# esp32_with_usbc_1st.net
KiCad netlist of a schematic drawn in Altium Designer
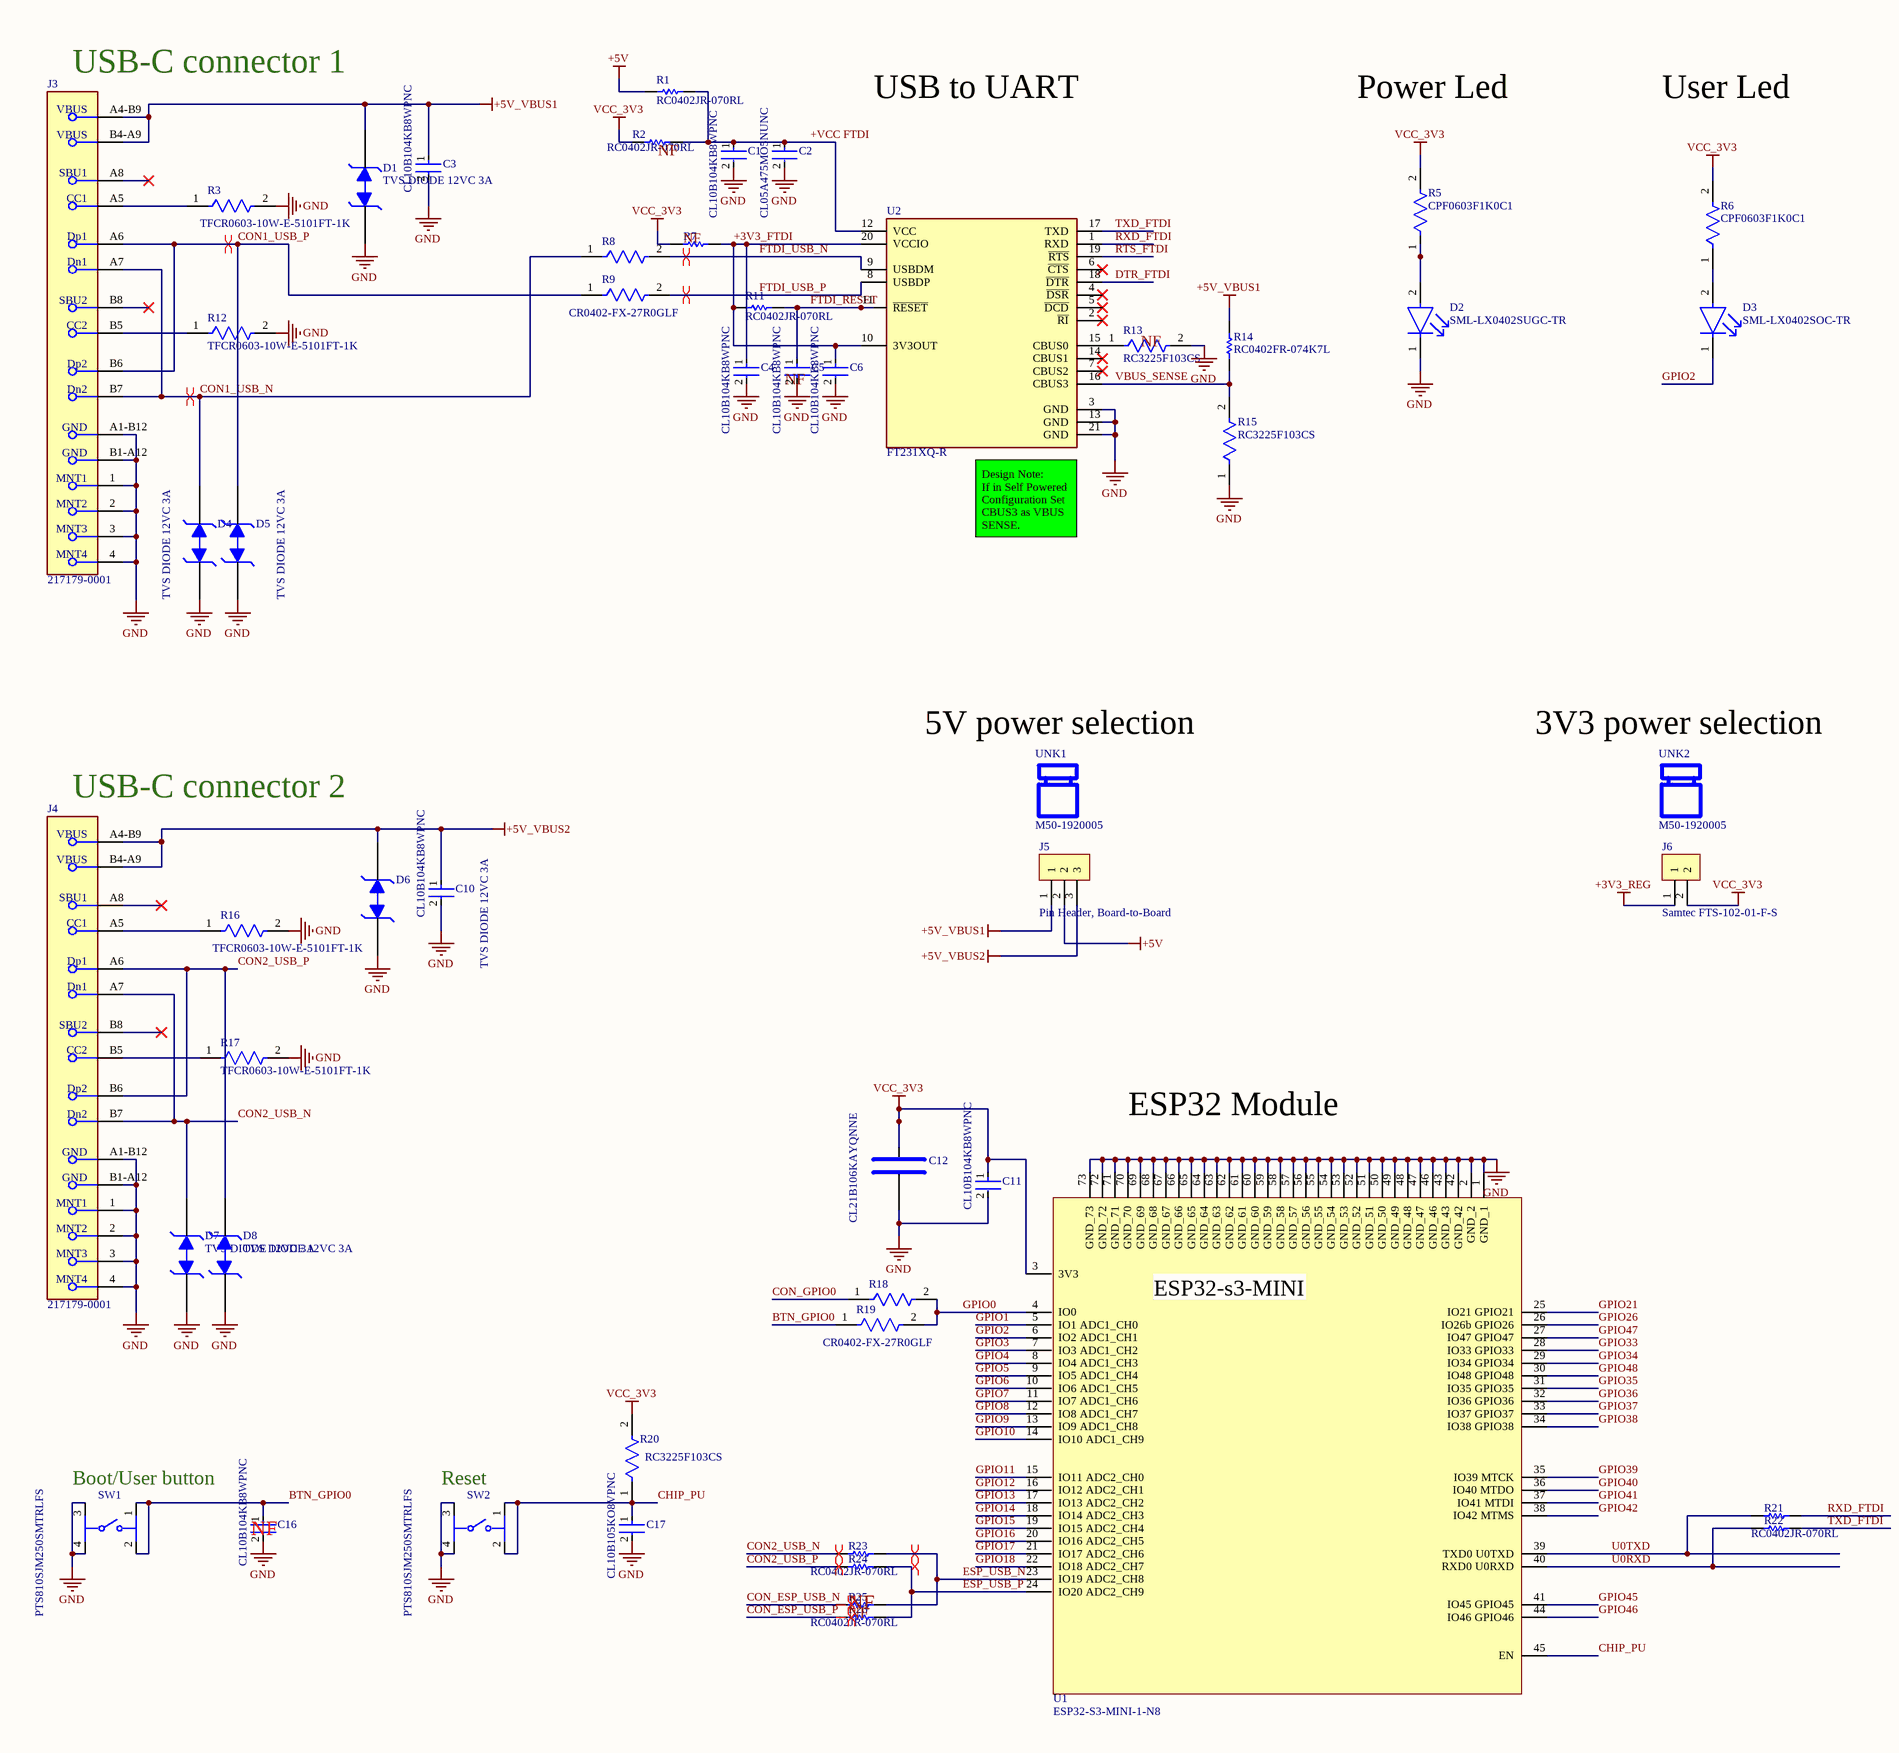
[diagram p0: esp32_with_usbc_1st.SchDoc, left]
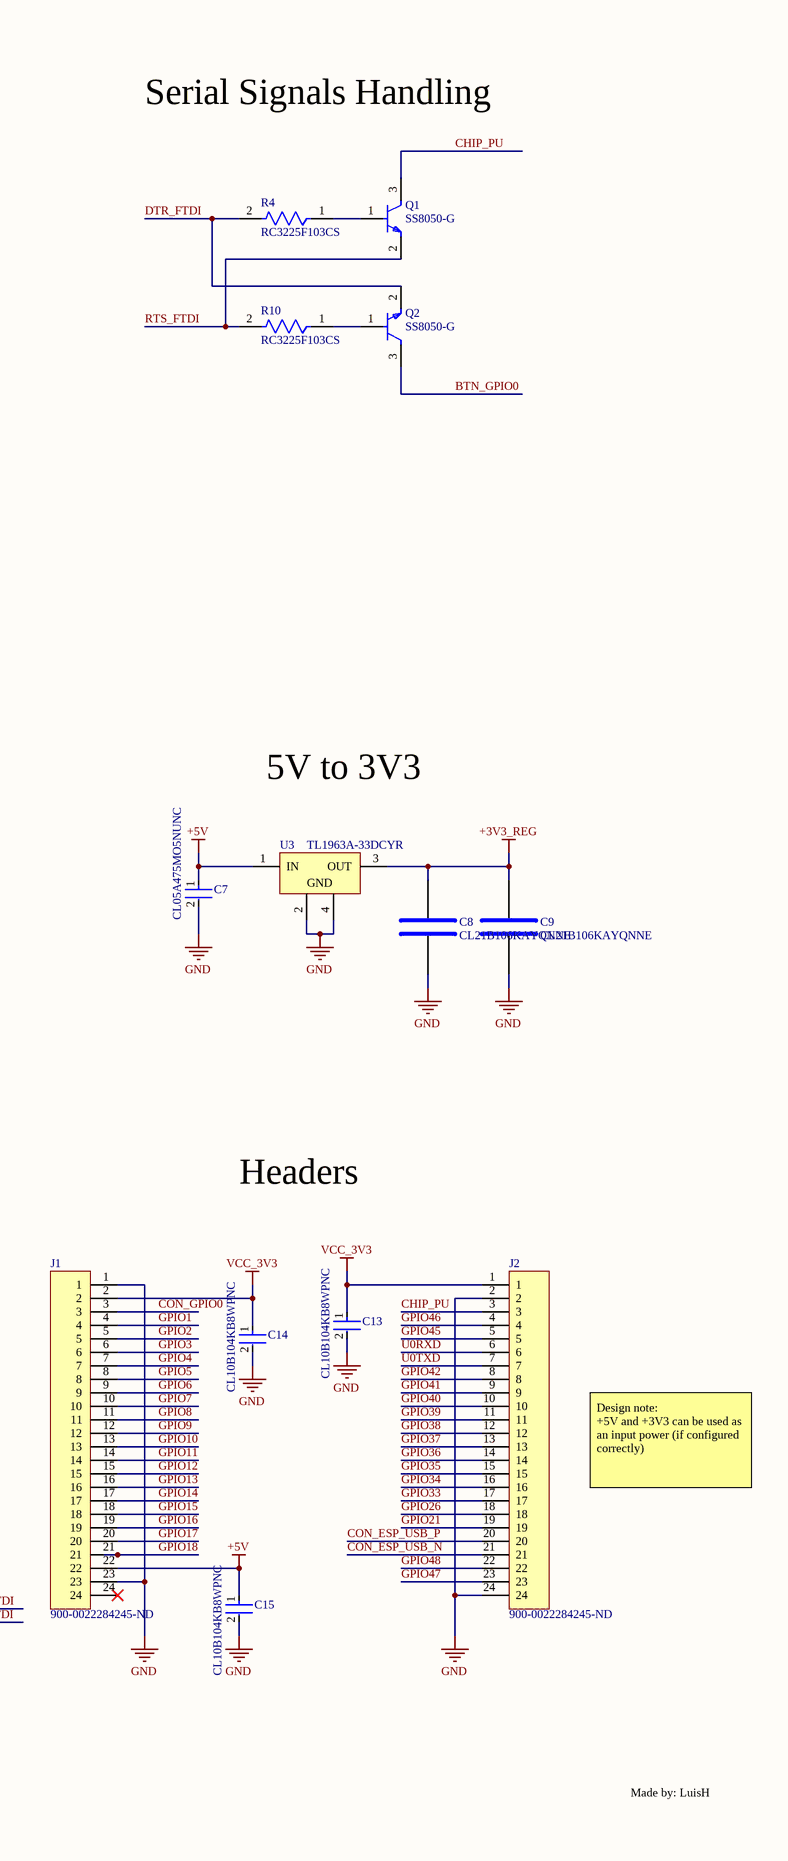
[diagram p1: esp32_with_usbc_1st.SchDoc, right]

(export (version "E")
  (design (tool "Eeschema 10.0.6"))
  (components
    (comp (ref "C1")
      (value "CL10B104KB8WPNC")
      (footprint "FP-CL10-IPC_A")
      (description "Cap Ceramic 100nF 50V X7R ±10% Pad SMD 0603 +125°C T/R")
      (fields (field (name "TOLERANCE") "10%"))
      (libsource (lib "Altium Content Vault") (part "b4654b650e69147ec39a6b967a45e02"))
    )
    (comp (ref "C2")
      (value "CL05A475MO5NUNC")
      (footprint "FP-CL829-IPC_C")
      (description "Cap Ceramic 4.7uF 16V X5R ±20% SMD 0402 +85°C Paper T/R")
      (fields (field (name "TOLERANCE") "20%"))
      (libsource (lib "Altium Content Vault") (part "b4654b650e69147ec39a6b967a45e02"))
    )
    (comp (ref "C3")
      (value "CL10B104KB8WPNC")
      (footprint "FP-CL10-IPC_A")
      (description "Cap Ceramic 100nF 50V X7R ±10% Pad SMD 0603 +125°C T/R")
      (fields (field (name "TOLERANCE") "10%"))
      (libsource (lib "Altium Content Vault") (part "b4654b650e69147ec39a6b967a45e02"))
    )
    (comp (ref "C4")
      (value "CL10B104KB8WPNC")
      (footprint "FP-CL10-IPC_A")
      (description "Cap Ceramic 100nF 50V X7R ±10% Pad SMD 0603 +125°C T/R")
      (fields (field (name "TOLERANCE") "10%"))
      (libsource (lib "Altium Content Vault") (part "b4654b650e69147ec39a6b967a45e02"))
    )
    (comp (ref "C5")
      (value "CL10B104KB8WPNC")
      (footprint "FP-CL10-IPC_A")
      (description "Cap Ceramic 100nF 50V X7R ±10% Pad SMD 0603 +125°C T/R")
      (fields (field (name "TOLERANCE") "10%"))
      (libsource (lib "Altium Content Vault") (part "b4654b650e69147ec39a6b967a45e02"))
    )
    (comp (ref "C6")
      (value "CL10B104KB8WPNC")
      (footprint "FP-CL10-IPC_A")
      (description "Cap Ceramic 100nF 50V X7R ±10% Pad SMD 0603 +125°C T/R")
      (fields (field (name "TOLERANCE") "10%"))
      (libsource (lib "Altium Content Vault") (part "b4654b650e69147ec39a6b967a45e02"))
    )
    (comp (ref "C7")
      (value "CL05A475MO5NUNC")
      (footprint "FP-CL829-IPC_C")
      (description "Cap Ceramic 4.7uF 16V X5R ±20% SMD 0402 +85°C Paper T/R")
      (fields (field (name "TOLERANCE") "20%"))
      (libsource (lib "Altium Content Vault") (part "b4654b650e69147ec39a6b967a45e02"))
    )
    (comp (ref "C8")
      (value "CL21B106KAYQNNE")
      (footprint "CAP_CL21B106KAYQNNE_SAM-L")
      (description "25V 10uF X7R 卤10% 0805 Multilayer Ceramic Capacitors MLCC - SMD/SMT ROHS")
      (fields (field (name "MANUFACTURER") "Samsung Electro-Mechanics") (field (name "TOLERANCE") "10%"))
      (libsource (lib "esp32_with_usbc") (part "CL21B106KAYQNNE"))
    )
    (comp (ref "C9")
      (value "CL21B106KAYQNNE")
      (footprint "CAP_CL21B106KAYQNNE_SAM-L")
      (description "25V 10uF X7R 卤10% 0805 Multilayer Ceramic Capacitors MLCC - SMD/SMT ROHS")
      (fields (field (name "MANUFACTURER") "Samsung Electro-Mechanics") (field (name "TOLERANCE") "10%"))
      (libsource (lib "esp32_with_usbc") (part "CL21B106KAYQNNE"))
    )
    (comp (ref "C10")
      (value "CL10B104KB8WPNC")
      (footprint "FP-CL10-IPC_A")
      (description "Cap Ceramic 100nF 50V X7R ±10% Pad SMD 0603 +125°C T/R")
      (fields (field (name "TOLERANCE") "10%"))
      (libsource (lib "Altium Content Vault") (part "b4654b650e69147ec39a6b967a45e02"))
    )
    (comp (ref "C11")
      (value "CL10B104KB8WPNC")
      (footprint "FP-CL10-IPC_A")
      (description "Cap Ceramic 100nF 50V X7R ±10% Pad SMD 0603 +125°C T/R")
      (fields (field (name "TOLERANCE") "10%"))
      (libsource (lib "Altium Content Vault") (part "b4654b650e69147ec39a6b967a45e02"))
    )
    (comp (ref "C12")
      (value "CL21B106KAYQNNE")
      (footprint "CAP_CL21B106KAYQNNE_SAM-L")
      (description "25V 10uF X7R 卤10% 0805 Multilayer Ceramic Capacitors MLCC - SMD/SMT ROHS")
      (fields (field (name "MANUFACTURER") "Samsung Electro-Mechanics") (field (name "TOLERANCE") "10%"))
      (libsource (lib "esp32_with_usbc") (part "CL21B106KAYQNNE"))
    )
    (comp (ref "C13")
      (value "CL10B104KB8WPNC")
      (footprint "FP-CL10-IPC_A")
      (description "Cap Ceramic 100nF 50V X7R ±10% Pad SMD 0603 +125°C T/R")
      (fields (field (name "TOLERANCE") "10%"))
      (libsource (lib "Altium Content Vault") (part "b4654b650e69147ec39a6b967a45e02"))
    )
    (comp (ref "C14")
      (value "CL10B104KB8WPNC")
      (footprint "FP-CL10-IPC_A")
      (description "Cap Ceramic 100nF 50V X7R ±10% Pad SMD 0603 +125°C T/R")
      (fields (field (name "TOLERANCE") "10%"))
      (libsource (lib "Altium Content Vault") (part "b4654b650e69147ec39a6b967a45e02"))
    )
    (comp (ref "C15")
      (value "CL10B104KB8WPNC")
      (footprint "FP-CL10-IPC_A")
      (description "Cap Ceramic 100nF 50V X7R ±10% Pad SMD 0603 +125°C T/R")
      (fields (field (name "TOLERANCE") "10%"))
      (libsource (lib "Altium Content Vault") (part "b4654b650e69147ec39a6b967a45e02"))
    )
    (comp (ref "C16")
      (value "CL10B104KB8WPNC")
      (footprint "FP-CL10-IPC_A")
      (description "Cap Ceramic 100nF 50V X7R ±10% Pad SMD 0603 +125°C T/R")
      (fields (field (name "TOLERANCE") "10%"))
      (libsource (lib "Altium Content Vault") (part "b4654b650e69147ec39a6b967a45e02"))
    )
    (comp (ref "C17")
      (value "CL10B105KO8VPNC")
      (footprint "FP-CL10-IPC_C")
      (description "Cap Ceramic 1uF 16V X7R ±10% Pad SMD 0603 +125°C T/R")
      (fields (field (name "TOLERANCE") "10%"))
      (libsource (lib "Altium Content Vault") (part "b4654b650e69147ec39a6b967a45e02"))
    )
    (comp (ref "D1")
      (value "TVS DIODE 12VC 3A")
      (footprint "RTVS_SOD882_LTF")
      (description "TVS DIODE 12VC 3A SOD882 / ESD Suppressor TVS Bi-Dir 5.3V Automotive 2-Pin SOD-882 T/R")
      (fields
        (field (name "MANUFACTURER") "Littelfuse")
        (field (name "MANUFACTURER PART NUMBER") "AQ3045-01ETG")
      )
      (libsource (lib "esp32_with_usbc") (part "AQ3045-01ETG"))
    )
    (comp (ref "D2")
      (value "SML-LX0402SUGC-TR")
      (footprint "FP-SML-LX0402SUGC-TR-MFG")
      (description "LED GREEN CLEAR SMD")
      (libsource (lib "Altium Content Vault") (part "8706943c75ba83719d021d2fdc84c58"))
    )
    (comp (ref "D3")
      (value "SML-LX0402SOC-TR")
      (footprint "FP-SML-LX0402SOC-TR-MFG")
      (description "LED ORANGE CLEAR SMD")
      (libsource (lib "Altium Content Vault") (part "8706943c75ba83719d021d2fdc84c58"))
    )
    (comp (ref "D4")
      (value "TVS DIODE 12VC 3A")
      (footprint "RTVS_SOD882_LTF")
      (description "TVS DIODE 12VC 3A SOD882 / ESD Suppressor TVS Bi-Dir 5.3V Automotive 2-Pin SOD-882 T/R")
      (fields
        (field (name "MANUFACTURER") "Littelfuse")
        (field (name "MANUFACTURER PART NUMBER") "AQ3045-01ETG")
      )
      (libsource (lib "esp32_with_usbc") (part "AQ3045-01ETG"))
    )
    (comp (ref "D5")
      (value "TVS DIODE 12VC 3A")
      (footprint "RTVS_SOD882_LTF")
      (description "TVS DIODE 12VC 3A SOD882 / ESD Suppressor TVS Bi-Dir 5.3V Automotive 2-Pin SOD-882 T/R")
      (fields
        (field (name "MANUFACTURER") "Littelfuse")
        (field (name "MANUFACTURER PART NUMBER") "AQ3045-01ETG")
      )
      (libsource (lib "esp32_with_usbc") (part "AQ3045-01ETG"))
    )
    (comp (ref "D6")
      (value "TVS DIODE 12VC 3A")
      (footprint "RTVS_SOD882_LTF")
      (description "TVS DIODE 12VC 3A SOD882 / ESD Suppressor TVS Bi-Dir 5.3V Automotive 2-Pin SOD-882 T/R")
      (fields
        (field (name "MANUFACTURER") "Littelfuse")
        (field (name "MANUFACTURER PART NUMBER") "AQ3045-01ETG")
      )
      (libsource (lib "esp32_with_usbc") (part "AQ3045-01ETG"))
    )
    (comp (ref "D7")
      (value "TVS DIODE 12VC 3A")
      (footprint "RTVS_SOD882_LTF")
      (description "TVS DIODE 12VC 3A SOD882 / ESD Suppressor TVS Bi-Dir 5.3V Automotive 2-Pin SOD-882 T/R")
      (fields
        (field (name "MANUFACTURER") "Littelfuse")
        (field (name "MANUFACTURER PART NUMBER") "AQ3045-01ETG")
      )
      (libsource (lib "esp32_with_usbc") (part "AQ3045-01ETG"))
    )
    (comp (ref "D8")
      (value "TVS DIODE 12VC 3A")
      (footprint "RTVS_SOD882_LTF")
      (description "TVS DIODE 12VC 3A SOD882 / ESD Suppressor TVS Bi-Dir 5.3V Automotive 2-Pin SOD-882 T/R")
      (fields
        (field (name "MANUFACTURER") "Littelfuse")
        (field (name "MANUFACTURER PART NUMBER") "AQ3045-01ETG")
      )
      (libsource (lib "esp32_with_usbc") (part "AQ3045-01ETG"))
    )
    (comp (ref "J1")
      (value "900-0022284245-ND")
      (footprint "CONN_SD-42375-001_M295_24_MOL")
      (fields
        (field (name "MANUFACTURER") "Molex")
        (field (name "MANUFACTURER PART NUMBER") "22-28-4245")
        (field (name "LCSC PART NUMBER") "C7145888")
      )
      (libsource (lib "") (part "22-28-4245_1"))
    )
    (comp (ref "J2")
      (value "900-0022284245-ND")
      (footprint "CONN_SD-42375-001_M295_24_MOL")
      (fields
        (field (name "MANUFACTURER") "Molex")
        (field (name "MANUFACTURER PART NUMBER") "22-28-4245")
        (field (name "LCSC PART NUMBER") "C7145888")
      )
      (libsource (lib "esp32_with_usbc") (part "22-28-4245"))
    )
    (comp (ref "J3")
      (value "217179-0001")
      (footprint "FP-2171790001-MFG")
      (description "USB Connector, 16 Contact(s), Female, Right Angle, Surface Mount Terminal, Locking, Receptacle")
      (fields (field (name "MANUFACTURER") "Molex"))
      (libsource (lib "esp32_with_usbc") (part "217179-0001"))
    )
    (comp (ref "J4")
      (value "217179-0001")
      (footprint "FP-2171790001-MFG")
      (description "USB Connector, 16 Contact(s), Female, Right Angle, Surface Mount Terminal, Locking, Receptacle")
      (fields (field (name "MANUFACTURER") "Molex"))
      (libsource (lib "esp32_with_usbc") (part "217179-0001"))
    )
    (comp (ref "J5")
      (value "Pin Header, Board-to-Board")
      (footprint "HDR_1x3_1.27mm")
      (description "Pin Header, Board-to-Board, Wire-to-Board, 3.4 A, 1.27 mm, 1 Rows, 3 Contacts, Through Hole")
      (fields
        (field (name "MANUFACTURER") "Samtec")
        (field (name "MANUFACTURER PART NUMBER") "FTS-103-01-F-S")
      )
      (libsource (lib "esp32_with_usbc") (part "FTS-103-01-F-S"))
    )
    (comp (ref "J6")
      (value "Samtec FTS-102-01-F-S")
      (footprint "HDR_1x2_1.27mm")
      (description "Pin Header, Board-to-Board, 1.27 mm, 1 Rows, 2 Contacts, Through Hole Straight, FTS Series")
      (fields
        (field (name "MANUFACTURER") "Samtec")
        (field (name "MANUFACTURER PART NUMBER") "FTS-102-01-F-S")
      )
      (libsource (lib "esp32_with_usbc") (part "FTS-102-01-F-S"))
    )
    (comp (ref "Q1")
      (value "SS8050-G")
      (footprint "FP-SS8050-G-MFG")
      (description "NPN TRANSISTOR 1.5A 40V SOT-23 R")
      (libsource (lib "Altium Content Vault") (part "2a1388f82443b098dcd57d24ac7632d"))
    )
    (comp (ref "Q2")
      (value "SS8050-G")
      (footprint "FP-SS8050-G-MFG")
      (description "NPN TRANSISTOR 1.5A 40V SOT-23 R")
      (libsource (lib "Altium Content Vault") (part "2a1388f82443b098dcd57d24ac7632d"))
    )
    (comp (ref "R1")
      (value "RC0402JR-070RL")
      (footprint "RESC1005X40X25NL05T10")
      (fields (field (name "MANUFACTURER") "Yageo / Phycomp"))
      (libsource (lib "Altium Content Vault") (part "RES"))
    )
    (comp (ref "R2")
      (value "RC0402JR-070RL")
      (footprint "RESC1005X40X25NL05T10")
      (fields (field (name "MANUFACTURER") "Yageo / Phycomp"))
      (libsource (lib "Altium Content Vault") (part "RES"))
    )
    (comp (ref "R3")
      (value "TFCR0603-10W-E-5101FT-1K")
      (footprint "FP-TFCR0603-IPC_C")
      (description "RES Thin Film,  5.1kΩ, 1%, 0.1W, 25ppm/°C, 0603")
      (libsource (lib "Altium Content Vault") (part "1029c3af85768c4190bb7ad29bc67b5"))
    )
    (comp (ref "R4")
      (value "RC3225F103CS")
      (footprint "FP-RC3225-IPC_C")
      (description "Res Thick Film 1210 10kΩ 1% 0.333W ±100ppm/°C Pad SMD T/R")
      (libsource (lib "Altium Content Vault") (part "1029c3af85768c4190bb7ad29bc67b5"))
    )
    (comp (ref "R5")
      (value "CPF0603F1K0C1")
      (footprint "FP-CPF0603-MFG")
      (description "RES SMD 1.0KΩ 1% 1/16W 0603")
      (fields
        (field (name "OCTOPART") "https://octopart.com/cpf0603f1k0c1-te+connectivity-42013134")
        (field (name "TOLERANCE") "1%")
      )
      (libsource (lib "Altium Content Vault") (part "1029c3af85768c4190bb7ad29bc67b5"))
    )
    (comp (ref "R6")
      (value "CPF0603F1K0C1")
      (footprint "FP-CPF0603-MFG")
      (description "RES SMD 1.0KΩ 1% 1/16W 0603")
      (fields
        (field (name "OCTOPART") "https://octopart.com/cpf0603f1k0c1-te+connectivity-42013134")
        (field (name "TOLERANCE") "1%")
      )
      (libsource (lib "Altium Content Vault") (part "1029c3af85768c4190bb7ad29bc67b5"))
    )
    (comp (ref "R7")
      (value "RC0402JR-070RL")
      (footprint "RESC1005X40X25NL05T10")
      (fields (field (name "MANUFACTURER") "Yageo / Phycomp"))
      (libsource (lib "Altium Content Vault") (part "RES"))
    )
    (comp (ref "R8")
      (value "CR0402-FX-27R0GLF")
      (footprint "FP-CR0402-MFG")
      (description "Thick Film Chip Resistors 0402 27Ω 0.0625W 1% 100ppm/°C")
      (fields (field (name "TOLERANCE") "1%"))
      (libsource (lib "Altium Content Vault") (part "1029c3af85768c4190bb7ad29bc67b5"))
    )
    (comp (ref "R9")
      (value "CR0402-FX-27R0GLF")
      (footprint "FP-CR0402-MFG")
      (description "Thick Film Chip Resistors 0402 27Ω 0.0625W 1% 100ppm/°C")
      (fields (field (name "TOLERANCE") "1%"))
      (libsource (lib "Altium Content Vault") (part "1029c3af85768c4190bb7ad29bc67b5"))
    )
    (comp (ref "R10")
      (value "RC3225F103CS")
      (footprint "FP-RC3225-IPC_C")
      (description "Res Thick Film 1210 10kΩ 1% 0.333W ±100ppm/°C Pad SMD T/R")
      (libsource (lib "Altium Content Vault") (part "1029c3af85768c4190bb7ad29bc67b5"))
    )
    (comp (ref "R11")
      (value "RC0402JR-070RL")
      (footprint "RESC1005X40X25NL05T10")
      (fields (field (name "MANUFACTURER") "Yageo / Phycomp"))
      (libsource (lib "Altium Content Vault") (part "RES"))
    )
    (comp (ref "R12")
      (value "TFCR0603-10W-E-5101FT-1K")
      (footprint "FP-TFCR0603-IPC_C")
      (description "RES Thin Film,  5.1kΩ, 1%, 0.1W, 25ppm/°C, 0603")
      (libsource (lib "Altium Content Vault") (part "1029c3af85768c4190bb7ad29bc67b5"))
    )
    (comp (ref "R13")
      (value "RC3225F103CS")
      (footprint "FP-RC3225-IPC_C")
      (description "Res Thick Film 1210 10kΩ 1% 0.333W ±100ppm/°C Pad SMD T/R")
      (libsource (lib "Altium Content Vault") (part "1029c3af85768c4190bb7ad29bc67b5"))
    )
    (comp (ref "R14")
      (value "RC0402FR-074K7L")
      (footprint "RESC1005X40X25NL05T10")
      (fields (field (name "MANUFACTURER") "Yageo / Phycomp"))
      (libsource (lib "Altium Content Vault") (part "RES"))
    )
    (comp (ref "R15")
      (value "RC3225F103CS")
      (footprint "FP-RC3225-IPC_C")
      (description "Res Thick Film 1210 10kΩ 1% 0.333W ±100ppm/°C Pad SMD T/R")
      (libsource (lib "Altium Content Vault") (part "1029c3af85768c4190bb7ad29bc67b5"))
    )
    (comp (ref "R16")
      (value "TFCR0603-10W-E-5101FT-1K")
      (footprint "FP-TFCR0603-IPC_C")
      (description "RES Thin Film,  5.1kΩ, 1%, 0.1W, 25ppm/°C, 0603")
      (libsource (lib "Altium Content Vault") (part "1029c3af85768c4190bb7ad29bc67b5"))
    )
    (comp (ref "R17")
      (value "TFCR0603-10W-E-5101FT-1K")
      (footprint "FP-TFCR0603-IPC_C")
      (description "RES Thin Film,  5.1kΩ, 1%, 0.1W, 25ppm/°C, 0603")
      (libsource (lib "Altium Content Vault") (part "1029c3af85768c4190bb7ad29bc67b5"))
    )
    (comp (ref "R18")
      (value "CR0402-FX-27R0GLF")
      (footprint "FP-CR0402-MFG")
      (description "Thick Film Chip Resistors 0402 27Ω 0.0625W 1% 100ppm/°C")
      (fields (field (name "TOLERANCE") "1%"))
      (libsource (lib "Altium Content Vault") (part "1029c3af85768c4190bb7ad29bc67b5"))
    )
    (comp (ref "R19")
      (value "CR0402-FX-27R0GLF")
      (footprint "FP-CR0402-MFG")
      (description "Thick Film Chip Resistors 0402 27Ω 0.0625W 1% 100ppm/°C")
      (fields (field (name "TOLERANCE") "1%"))
      (libsource (lib "Altium Content Vault") (part "1029c3af85768c4190bb7ad29bc67b5"))
    )
    (comp (ref "R20")
      (value "RC3225F103CS")
      (footprint "FP-RC3225-IPC_C")
      (description "Res Thick Film 1210 10kΩ 1% 0.333W ±100ppm/°C Pad SMD T/R")
      (libsource (lib "Altium Content Vault") (part "1029c3af85768c4190bb7ad29bc67b5"))
    )
    (comp (ref "R21")
      (value "RC0402JR-070RL")
      (footprint "RESC1005X40X25NL05T10")
      (fields (field (name "MANUFACTURER") "Yageo / Phycomp"))
      (libsource (lib "Altium Content Vault") (part "RES"))
    )
    (comp (ref "R22")
      (value "RC0402JR-070RL")
      (footprint "RESC1005X40X25NL05T10")
      (fields (field (name "MANUFACTURER") "Yageo / Phycomp"))
      (libsource (lib "Altium Content Vault") (part "RES"))
    )
    (comp (ref "R23")
      (value "RC0402JR-070RL")
      (footprint "RESC1005X40X25NL05T10")
      (fields (field (name "MANUFACTURER") "Yageo / Phycomp"))
      (libsource (lib "Altium Content Vault") (part "RES"))
    )
    (comp (ref "R24")
      (value "RC0402JR-070RL")
      (footprint "RESC1005X40X25NL05T10")
      (fields (field (name "MANUFACTURER") "Yageo / Phycomp"))
      (libsource (lib "Altium Content Vault") (part "RES"))
    )
    (comp (ref "R25")
      (value "RC0402JR-070RL")
      (footprint "RESC1005X40X25NL05T10")
      (fields (field (name "MANUFACTURER") "Yageo / Phycomp"))
      (libsource (lib "Altium Content Vault") (part "RES"))
    )
    (comp (ref "R26")
      (value "RC0402JR-070RL")
      (footprint "RESC1005X40X25NL05T10")
      (fields (field (name "MANUFACTURER") "Yageo / Phycomp"))
      (libsource (lib "Altium Content Vault") (part "RES"))
    )
    (comp (ref "SW1")
      (value "PTS810SJM250SMTRLFS")
      (footprint "FP-PTS810SJM250SMTRLFS-MFG")
      (description "SWITCH TACTILE SPST-NO 0.05A 16V")
      (libsource (lib "Altium Content Vault") (part "1adf0dd01260c80cf25a44bfd6b99ba"))
    )
    (comp (ref "SW2")
      (value "PTS810SJM250SMTRLFS")
      (footprint "FP-PTS810SJM250SMTRLFS-MFG")
      (description "SWITCH TACTILE SPST-NO 0.05A 16V")
      (libsource (lib "Altium Content Vault") (part "1adf0dd01260c80cf25a44bfd6b99ba"))
    )
    (comp (ref "U1")
      (value "ESP32-S3-MINI-1-N8")
      (footprint "XCVR_ESP32-S3-MINI-1-N8")
      (description "SMD module, ESP32-S3FN8, 8 MB SPI flash, PCB antenna")
      (fields (field (name "MANUFACTURER") "Espressif Systems") (field (name "LCSC PART NUMBER") "C2913206"))
      (libsource (lib "esp32_with_usbc") (part "ESP32-S3-MINI-1-N8"))
    )
    (comp (ref "U2")
      (value "FT231XQ-R")
      (footprint "FP-QFN-20-IPC_B")
      (description "IC USB SERIAL FULL UART 20QFN")
      (fields (field (name "LCSC PART NUMBER") "C132159"))
      (libsource (lib "esp32_with_usbc") (part "FT231XQ-R"))
    )
    (comp (ref "U3")
      (value "TL1963A-33DCYR")
      (footprint "DCY0004A_N")
      (fields (field (name "MANUFACTURER") "Texas Instruments"))
      (libsource (lib "Altium Content Vault") (part "TI-TL1963A-XXDCY4"))
    )
    (comp (ref "UNK1")
      (value "M50-1920005")
      (description "Jumper (Busbar), Jumper Socket, Pin Hdrs; ¦Harwin M50-1920005")
      (fields (field (name "MANUFACTURER") "Harwin") (field (name "LCSC PART NUMBER") "C6985646"))
      (libsource (lib "esp32_with_usbc") (part "M50-1920005"))
    )
    (comp (ref "UNK2")
      (value "M50-1920005")
      (description "Jumper (Busbar), Jumper Socket, Pin Hdrs; ¦Harwin M50-1920005")
      (fields (field (name "MANUFACTURER") "Harwin") (field (name "LCSC PART NUMBER") "C6985646"))
      (libsource (lib "esp32_with_usbc") (part "M50-1920005"))
    )
  )
  (nets
    (net (code "1") (name "+3V3_REG") (class "Default")
      (node (ref "C8") (pin "2") (pinfunction "2_2") (pintype "passive"))
      (node (ref "C9") (pin "2") (pinfunction "2_2") (pintype "passive"))
      (node (ref "J6") (pin "1") (pinfunction "1_1") (pintype "passive"))
      (node (ref "U3") (pin "3") (pinfunction "OUT_3") (pintype "power_in"))
    )
    (net (code "2") (name "+5V") (class "Default")
      (node (ref "C15") (pin "1") (pinfunction "1_1") (pintype "passive"))
      (node (ref "C7") (pin "1") (pinfunction "1_1") (pintype "passive"))
      (node (ref "J1") (pin "22") (pinfunction "22_22") (pintype "passive"))
      (node (ref "J5") (pin "2") (pinfunction "2_2") (pintype "passive"))
      (node (ref "R1") (pin "1") (pinfunction "1_1") (pintype "passive"))
      (node (ref "U3") (pin "1") (pinfunction "IN_1") (pintype "power_in"))
    )
    (net (code "3") (name "+5V_VBUS1") (class "Default")
      (node (ref "C3") (pin "1") (pinfunction "1_1") (pintype "passive"))
      (node (ref "D1") (pin "2") (pinfunction "2_2") (pintype "passive"))
      (node (ref "J3") (pin "A4-B9") (pinfunction "VBUS_A4-B9") (pintype "passive"))
      (node (ref "J3") (pin "B4-A9") (pinfunction "VBUS_B4-A9") (pintype "passive"))
      (node (ref "J5") (pin "1") (pinfunction "1_1") (pintype "passive"))
      (node (ref "R14") (pin "2") (pinfunction "2_2") (pintype "passive"))
    )
    (net (code "4") (name "+5V_VBUS2") (class "Default")
      (node (ref "C10") (pin "1") (pinfunction "1_1") (pintype "passive"))
      (node (ref "D6") (pin "2") (pinfunction "2_2") (pintype "passive"))
      (node (ref "J4") (pin "A4-B9") (pinfunction "VBUS_A4-B9") (pintype "passive"))
      (node (ref "J4") (pin "B4-A9") (pinfunction "VBUS_B4-A9") (pintype "passive"))
      (node (ref "J5") (pin "3") (pinfunction "3_3") (pintype "passive"))
    )
    (net (code "5") (name "/+3V3_FTDI") (class "Default")
      (node (ref "C4") (pin "1") (pinfunction "1_1") (pintype "passive"))
      (node (ref "C6") (pin "1") (pinfunction "1_1") (pintype "passive"))
      (node (ref "R11") (pin "1") (pinfunction "1_1") (pintype "passive"))
      (node (ref "R7") (pin "2") (pinfunction "2_2") (pintype "passive"))
      (node (ref "U2") (pin "10") (pinfunction "3V3OUT_10") (pintype "passive"))
      (node (ref "U2") (pin "20") (pinfunction "VCCIO_20") (pintype "power_in"))
    )
    (net (code "6") (name "/+VCC FTDI") (class "Default")
      (node (ref "C1") (pin "1") (pinfunction "1_1") (pintype "passive"))
      (node (ref "C2") (pin "1") (pinfunction "1_1") (pintype "passive"))
      (node (ref "R1") (pin "2") (pinfunction "2_2") (pintype "passive"))
      (node (ref "R2") (pin "2") (pinfunction "2_2") (pintype "passive"))
      (node (ref "U2") (pin "12") (pinfunction "VCC_12") (pintype "power_in"))
    )
    (net (code "7") (name "/BTN_GPIO0") (class "Default")
      (node (ref "C16") (pin "1") (pinfunction "1_1") (pintype "passive"))
      (node (ref "Q2") (pin "3") (pinfunction "C_3") (pintype "passive"))
      (node (ref "R19") (pin "1") (pinfunction "1_1") (pintype "passive"))
      (node (ref "SW1") (pin "1") (pinfunction "1_1") (pintype "passive"))
      (node (ref "SW1") (pin "2") (pinfunction "2_2") (pintype "passive"))
    )
    (net (code "8") (name "/CHIP_PU") (class "Default")
      (node (ref "C17") (pin "1") (pinfunction "1_1") (pintype "passive"))
      (node (ref "J2") (pin "3") (pinfunction "3_3") (pintype "passive"))
      (node (ref "Q1") (pin "3") (pinfunction "C_3") (pintype "passive"))
      (node (ref "R20") (pin "1") (pinfunction "1_1") (pintype "passive"))
      (node (ref "SW2") (pin "1") (pinfunction "1_1") (pintype "passive"))
      (node (ref "SW2") (pin "2") (pinfunction "2_2") (pintype "passive"))
      (node (ref "U1") (pin "45") (pinfunction "EN_45") (pintype "passive"))
    )
    (net (code "9") (name "/CON1_USB_N") (class "Default")
      (node (ref "D4") (pin "2") (pinfunction "2_2") (pintype "passive"))
      (node (ref "J3") (pin "A7") (pinfunction "Dn1_A7") (pintype "passive"))
      (node (ref "J3") (pin "B7") (pinfunction "Dn2_B7") (pintype "passive"))
      (node (ref "R8") (pin "1") (pinfunction "1_1") (pintype "passive"))
    )
    (net (code "10") (name "/CON1_USB_P") (class "Default")
      (node (ref "D5") (pin "2") (pinfunction "2_2") (pintype "passive"))
      (node (ref "J3") (pin "A6") (pinfunction "Dp1_A6") (pintype "passive"))
      (node (ref "J3") (pin "B6") (pinfunction "Dp2_B6") (pintype "passive"))
      (node (ref "R9") (pin "1") (pinfunction "1_1") (pintype "passive"))
    )
    (net (code "11") (name "/CON2_USB_N") (class "Default")
      (node (ref "D7") (pin "2") (pinfunction "2_2") (pintype "passive"))
      (node (ref "J4") (pin "A7") (pinfunction "Dn1_A7") (pintype "passive"))
      (node (ref "J4") (pin "B7") (pinfunction "Dn2_B7") (pintype "passive"))
      (node (ref "R23") (pin "1") (pinfunction "1_1") (pintype "passive"))
    )
    (net (code "12") (name "/CON2_USB_P") (class "Default")
      (node (ref "D8") (pin "2") (pinfunction "2_2") (pintype "passive"))
      (node (ref "J4") (pin "A6") (pinfunction "Dp1_A6") (pintype "passive"))
      (node (ref "J4") (pin "B6") (pinfunction "Dp2_B6") (pintype "passive"))
      (node (ref "R24") (pin "1") (pinfunction "1_1") (pintype "passive"))
    )
    (net (code "13") (name "/CON_ESP_USB_N") (class "Default")
      (node (ref "J2") (pin "21") (pinfunction "21_21") (pintype "passive"))
      (node (ref "R25") (pin "1") (pinfunction "1_1") (pintype "passive"))
    )
    (net (code "14") (name "/CON_ESP_USB_P") (class "Default")
      (node (ref "J2") (pin "20") (pinfunction "20_20") (pintype "passive"))
      (node (ref "R26") (pin "1") (pinfunction "1_1") (pintype "passive"))
    )
    (net (code "15") (name "/CON_GPIO0") (class "Default")
      (node (ref "J1") (pin "3") (pinfunction "3_3") (pintype "passive"))
      (node (ref "R18") (pin "1") (pinfunction "1_1") (pintype "passive"))
    )
    (net (code "16") (name "/DTR_FTDI") (class "Default")
      (node (ref "Q2") (pin "2") (pinfunction "E_2") (pintype "passive"))
      (node (ref "R4") (pin "2") (pinfunction "2_2") (pintype "passive"))
      (node (ref "U2") (pin "18") (pinfunction "~{DTR}_18") (pintype "passive"))
    )
    (net (code "17") (name "/ESP_USB_N") (class "Default")
      (node (ref "R23") (pin "2") (pinfunction "2_2") (pintype "passive"))
      (node (ref "R25") (pin "2") (pinfunction "2_2") (pintype "passive"))
      (node (ref "U1") (pin "23") (pinfunction "IO19_ADC2_CH8_23") (pintype "passive"))
    )
    (net (code "18") (name "/ESP_USB_P") (class "Default")
      (node (ref "R24") (pin "2") (pinfunction "2_2") (pintype "passive"))
      (node (ref "R26") (pin "2") (pinfunction "2_2") (pintype "passive"))
      (node (ref "U1") (pin "24") (pinfunction "IO20_ADC2_CH9_24") (pintype "passive"))
    )
    (net (code "19") (name "/FTDI_RESET") (class "Default")
      (node (ref "C5") (pin "1") (pinfunction "1_1") (pintype "passive"))
      (node (ref "R11") (pin "2") (pinfunction "2_2") (pintype "passive"))
      (node (ref "U2") (pin "11") (pinfunction "~{RESET}_11") (pintype "passive"))
    )
    (net (code "20") (name "/FTDI_USB_N") (class "Default")
      (node (ref "R8") (pin "2") (pinfunction "2_2") (pintype "passive"))
      (node (ref "U2") (pin "9") (pinfunction "USBDM_9") (pintype "passive"))
    )
    (net (code "21") (name "/FTDI_USB_P") (class "Default")
      (node (ref "R9") (pin "2") (pinfunction "2_2") (pintype "passive"))
      (node (ref "U2") (pin "8") (pinfunction "USBDP_8") (pintype "passive"))
    )
    (net (code "22") (name "/GPIO0") (class "Default")
      (node (ref "R18") (pin "2") (pinfunction "2_2") (pintype "passive"))
      (node (ref "R19") (pin "2") (pinfunction "2_2") (pintype "passive"))
      (node (ref "U1") (pin "4") (pinfunction "IO0_4") (pintype "passive"))
    )
    (net (code "23") (name "/GPIO1") (class "Default")
      (node (ref "J1") (pin "4") (pinfunction "4_4") (pintype "passive"))
      (node (ref "U1") (pin "5") (pinfunction "IO1_ADC1_CH0_5") (pintype "passive"))
    )
    (net (code "24") (name "/GPIO2") (class "Default")
      (node (ref "D3") (pin "1") (pinfunction "C_1") (pintype "passive"))
      (node (ref "J1") (pin "5") (pinfunction "5_5") (pintype "passive"))
      (node (ref "U1") (pin "6") (pinfunction "IO2_ADC1_CH1_6") (pintype "passive"))
    )
    (net (code "25") (name "/GPIO3") (class "Default")
      (node (ref "J1") (pin "6") (pinfunction "6_6") (pintype "passive"))
      (node (ref "U1") (pin "7") (pinfunction "IO3_ADC1_CH2_7") (pintype "passive"))
    )
    (net (code "26") (name "/GPIO4") (class "Default")
      (node (ref "J1") (pin "7") (pinfunction "7_7") (pintype "passive"))
      (node (ref "U1") (pin "8") (pinfunction "IO4_ADC1_CH3_8") (pintype "passive"))
    )
    (net (code "27") (name "/GPIO5") (class "Default")
      (node (ref "J1") (pin "8") (pinfunction "8_8") (pintype "passive"))
      (node (ref "U1") (pin "9") (pinfunction "IO5_ADC1_CH4_9") (pintype "passive"))
    )
    (net (code "28") (name "/GPIO6") (class "Default")
      (node (ref "J1") (pin "9") (pinfunction "9_9") (pintype "passive"))
      (node (ref "U1") (pin "10") (pinfunction "IO6_ADC1_CH5_10") (pintype "passive"))
    )
    (net (code "29") (name "/GPIO7") (class "Default")
      (node (ref "J1") (pin "10") (pinfunction "10_10") (pintype "passive"))
      (node (ref "U1") (pin "11") (pinfunction "IO7_ADC1_CH6_11") (pintype "passive"))
    )
    (net (code "30") (name "/GPIO8") (class "Default")
      (node (ref "J1") (pin "11") (pinfunction "11_11") (pintype "passive"))
      (node (ref "U1") (pin "12") (pinfunction "IO8_ADC1_CH7_12") (pintype "passive"))
    )
    (net (code "31") (name "/GPIO9") (class "Default")
      (node (ref "J1") (pin "12") (pinfunction "12_12") (pintype "passive"))
      (node (ref "U1") (pin "13") (pinfunction "IO9_ADC1_CH8_13") (pintype "passive"))
    )
    (net (code "32") (name "/GPIO10") (class "Default")
      (node (ref "J1") (pin "13") (pinfunction "13_13") (pintype "passive"))
      (node (ref "U1") (pin "14") (pinfunction "IO10_ADC1_CH9_14") (pintype "passive"))
    )
    (net (code "33") (name "/GPIO11") (class "Default")
      (node (ref "J1") (pin "14") (pinfunction "14_14") (pintype "passive"))
      (node (ref "U1") (pin "15") (pinfunction "IO11_ADC2_CH0_15") (pintype "passive"))
    )
    (net (code "34") (name "/GPIO12") (class "Default")
      (node (ref "J1") (pin "15") (pinfunction "15_15") (pintype "passive"))
      (node (ref "U1") (pin "16") (pinfunction "IO12_ADC2_CH1_16") (pintype "passive"))
    )
    (net (code "35") (name "/GPIO13") (class "Default")
      (node (ref "J1") (pin "16") (pinfunction "16_16") (pintype "passive"))
      (node (ref "U1") (pin "17") (pinfunction "IO13_ADC2_CH2_17") (pintype "passive"))
    )
    (net (code "36") (name "/GPIO14") (class "Default")
      (node (ref "J1") (pin "17") (pinfunction "17_17") (pintype "passive"))
      (node (ref "U1") (pin "18") (pinfunction "IO14_ADC2_CH3_18") (pintype "passive"))
    )
    (net (code "37") (name "/GPIO15") (class "Default")
      (node (ref "J1") (pin "18") (pinfunction "18_18") (pintype "passive"))
      (node (ref "U1") (pin "19") (pinfunction "IO15_ADC2_CH4_19") (pintype "passive"))
    )
    (net (code "38") (name "/GPIO16") (class "Default")
      (node (ref "J1") (pin "19") (pinfunction "19_19") (pintype "passive"))
      (node (ref "U1") (pin "20") (pinfunction "IO16_ADC2_CH5_20") (pintype "passive"))
    )
    (net (code "39") (name "/GPIO17") (class "Default")
      (node (ref "J1") (pin "20") (pinfunction "20_20") (pintype "passive"))
      (node (ref "U1") (pin "21") (pinfunction "IO17_ADC2_CH6_21") (pintype "passive"))
    )
    (net (code "40") (name "/GPIO18") (class "Default")
      (node (ref "J1") (pin "21") (pinfunction "21_21") (pintype "passive"))
      (node (ref "U1") (pin "22") (pinfunction "IO18_ADC2_CH7_22") (pintype "passive"))
    )
    (net (code "41") (name "/GPIO21") (class "Default")
      (node (ref "J2") (pin "19") (pinfunction "19_19") (pintype "passive"))
      (node (ref "U1") (pin "25") (pinfunction "IO21_GPIO21_25") (pintype "passive"))
    )
    (net (code "42") (name "/GPIO26") (class "Default")
      (node (ref "J2") (pin "18") (pinfunction "18_18") (pintype "passive"))
      (node (ref "U1") (pin "26") (pinfunction "IO26b_GPIO26_26") (pintype "passive"))
    )
    (net (code "43") (name "/GPIO33") (class "Default")
      (node (ref "J2") (pin "17") (pinfunction "17_17") (pintype "passive"))
      (node (ref "U1") (pin "28") (pinfunction "IO33_GPIO33_28") (pintype "passive"))
    )
    (net (code "44") (name "/GPIO34") (class "Default")
      (node (ref "J2") (pin "16") (pinfunction "16_16") (pintype "passive"))
      (node (ref "U1") (pin "29") (pinfunction "IO34_GPIO34_29") (pintype "passive"))
    )
    (net (code "45") (name "/GPIO35") (class "Default")
      (node (ref "J2") (pin "15") (pinfunction "15_15") (pintype "passive"))
      (node (ref "U1") (pin "31") (pinfunction "IO35_GPIO35_31") (pintype "passive"))
    )
    (net (code "46") (name "/GPIO36") (class "Default")
      (node (ref "J2") (pin "14") (pinfunction "14_14") (pintype "passive"))
      (node (ref "U1") (pin "32") (pinfunction "IO36_GPIO36_32") (pintype "passive"))
    )
    (net (code "47") (name "/GPIO37") (class "Default")
      (node (ref "J2") (pin "13") (pinfunction "13_13") (pintype "passive"))
      (node (ref "U1") (pin "33") (pinfunction "IO37_GPIO37_33") (pintype "passive"))
    )
    (net (code "48") (name "/GPIO38") (class "Default")
      (node (ref "J2") (pin "12") (pinfunction "12_12") (pintype "passive"))
      (node (ref "U1") (pin "34") (pinfunction "IO38_GPIO38_34") (pintype "passive"))
    )
    (net (code "49") (name "/GPIO39") (class "Default")
      (node (ref "J2") (pin "11") (pinfunction "11_11") (pintype "passive"))
      (node (ref "U1") (pin "35") (pinfunction "IO39_MTCK_35") (pintype "passive"))
    )
    (net (code "50") (name "/GPIO40") (class "Default")
      (node (ref "J2") (pin "10") (pinfunction "10_10") (pintype "passive"))
      (node (ref "U1") (pin "36") (pinfunction "IO40_MTDO_36") (pintype "passive"))
    )
    (net (code "51") (name "/GPIO41") (class "Default")
      (node (ref "J2") (pin "9") (pinfunction "9_9") (pintype "passive"))
      (node (ref "U1") (pin "37") (pinfunction "IO41_MTDI_37") (pintype "passive"))
    )
    (net (code "52") (name "/GPIO42") (class "Default")
      (node (ref "J2") (pin "8") (pinfunction "8_8") (pintype "passive"))
      (node (ref "U1") (pin "38") (pinfunction "IO42_MTMS_38") (pintype "passive"))
    )
    (net (code "53") (name "/GPIO45") (class "Default")
      (node (ref "J2") (pin "5") (pinfunction "5_5") (pintype "passive"))
      (node (ref "U1") (pin "41") (pinfunction "IO45_GPIO45_41") (pintype "passive"))
    )
    (net (code "54") (name "/GPIO46") (class "Default")
      (node (ref "J2") (pin "4") (pinfunction "4_4") (pintype "passive"))
      (node (ref "U1") (pin "44") (pinfunction "IO46_GPIO46_44") (pintype "passive"))
    )
    (net (code "55") (name "/GPIO47") (class "Default")
      (node (ref "J2") (pin "23") (pinfunction "23_23") (pintype "passive"))
      (node (ref "U1") (pin "27") (pinfunction "IO47_GPIO47_27") (pintype "passive"))
    )
    (net (code "56") (name "/GPIO48") (class "Default")
      (node (ref "J2") (pin "22") (pinfunction "22_22") (pintype "passive"))
      (node (ref "U1") (pin "30") (pinfunction "IO48_GPIO48_30") (pintype "passive"))
    )
    (net (code "57") (name "/RTS_FTDI") (class "Default")
      (node (ref "Q1") (pin "2") (pinfunction "E_2") (pintype "passive"))
      (node (ref "R10") (pin "2") (pinfunction "2_2") (pintype "passive"))
      (node (ref "U2") (pin "19") (pinfunction "~{RTS}_19") (pintype "passive"))
    )
    (net (code "58") (name "/RXD_FTDI") (class "Default")
      (node (ref "R21") (pin "2") (pinfunction "2_2") (pintype "passive"))
      (node (ref "U2") (pin "1") (pinfunction "RXD_1") (pintype "passive"))
    )
    (net (code "59") (name "/TXD_FTDI") (class "Default")
      (node (ref "R22") (pin "2") (pinfunction "2_2") (pintype "passive"))
      (node (ref "U2") (pin "17") (pinfunction "TXD_17") (pintype "passive"))
    )
    (net (code "60") (name "/U0RXD") (class "Default")
      (node (ref "J2") (pin "6") (pinfunction "6_6") (pintype "passive"))
      (node (ref "R22") (pin "1") (pinfunction "1_1") (pintype "passive"))
      (node (ref "U1") (pin "40") (pinfunction "RXD0_U0RXD_40") (pintype "passive"))
    )
    (net (code "61") (name "/U0TXD") (class "Default")
      (node (ref "J2") (pin "7") (pinfunction "7_7") (pintype "passive"))
      (node (ref "R21") (pin "1") (pinfunction "1_1") (pintype "passive"))
      (node (ref "U1") (pin "39") (pinfunction "TXD0_U0TXD_39") (pintype "passive"))
    )
    (net (code "62") (name "/VBUS_SENSE") (class "Default")
      (node (ref "R14") (pin "1") (pinfunction "1_1") (pintype "passive"))
      (node (ref "R15") (pin "2") (pinfunction "2_2") (pintype "passive"))
      (node (ref "U2") (pin "16") (pinfunction "CBUS3_16") (pintype "passive"))
    )
    (net (code "63") (name "GND") (class "Default")
      (node (ref "C1") (pin "2") (pinfunction "2_2") (pintype "passive"))
      (node (ref "C10") (pin "2") (pinfunction "2_2") (pintype "passive"))
      (node (ref "C11") (pin "2") (pinfunction "2_2") (pintype "passive"))
      (node (ref "C12") (pin "1") (pinfunction "1_1") (pintype "passive"))
      (node (ref "C13") (pin "2") (pinfunction "2_2") (pintype "passive"))
      (node (ref "C14") (pin "2") (pinfunction "2_2") (pintype "passive"))
      (node (ref "C15") (pin "2") (pinfunction "2_2") (pintype "passive"))
      (node (ref "C16") (pin "2") (pinfunction "2_2") (pintype "passive"))
      (node (ref "C17") (pin "2") (pinfunction "2_2") (pintype "passive"))
      (node (ref "C2") (pin "2") (pinfunction "2_2") (pintype "passive"))
      (node (ref "C3") (pin "2") (pinfunction "2_2") (pintype "passive"))
      (node (ref "C4") (pin "2") (pinfunction "2_2") (pintype "passive"))
      (node (ref "C5") (pin "2") (pinfunction "2_2") (pintype "passive"))
      (node (ref "C6") (pin "2") (pinfunction "2_2") (pintype "passive"))
      (node (ref "C7") (pin "2") (pinfunction "2_2") (pintype "passive"))
      (node (ref "C8") (pin "1") (pinfunction "1_1") (pintype "passive"))
      (node (ref "C9") (pin "1") (pinfunction "1_1") (pintype "passive"))
      (node (ref "D1") (pin "1") (pinfunction "1_1") (pintype "passive"))
      (node (ref "D2") (pin "1") (pinfunction "C_1") (pintype "passive"))
      (node (ref "D4") (pin "1") (pinfunction "1_1") (pintype "passive"))
      (node (ref "D5") (pin "1") (pinfunction "1_1") (pintype "passive"))
      (node (ref "D6") (pin "1") (pinfunction "1_1") (pintype "passive"))
      (node (ref "D7") (pin "1") (pinfunction "1_1") (pintype "passive"))
      (node (ref "D8") (pin "1") (pinfunction "1_1") (pintype "passive"))
      (node (ref "J1") (pin "1") (pinfunction "1_1") (pintype "passive"))
      (node (ref "J1") (pin "23") (pinfunction "23_23") (pintype "passive"))
      (node (ref "J2") (pin "2") (pinfunction "2_2") (pintype "passive"))
      (node (ref "J2") (pin "24") (pinfunction "24_24") (pintype "passive"))
      (node (ref "J3") (pin "1") (pinfunction "GND_1") (pintype "passive"))
      (node (ref "J3") (pin "2") (pinfunction "GND_2") (pintype "passive"))
      (node (ref "J3") (pin "3") (pinfunction "GND_3") (pintype "passive"))
      (node (ref "J3") (pin "4") (pinfunction "GND_4") (pintype "passive"))
      (node (ref "J3") (pin "A1-B12") (pinfunction "GND_A1-B12") (pintype "passive"))
      (node (ref "J3") (pin "B1-A12") (pinfunction "GND_B1-A12") (pintype "passive"))
      (node (ref "J4") (pin "1") (pinfunction "GND_1") (pintype "passive"))
      (node (ref "J4") (pin "2") (pinfunction "GND_2") (pintype "passive"))
      (node (ref "J4") (pin "3") (pinfunction "GND_3") (pintype "passive"))
      (node (ref "J4") (pin "4") (pinfunction "GND_4") (pintype "passive"))
      (node (ref "J4") (pin "A1-B12") (pinfunction "GND_A1-B12") (pintype "passive"))
      (node (ref "J4") (pin "B1-A12") (pinfunction "GND_B1-A12") (pintype "passive"))
      (node (ref "R12") (pin "2") (pinfunction "2_2") (pintype "passive"))
      (node (ref "R13") (pin "2") (pinfunction "2_2") (pintype "passive"))
      (node (ref "R15") (pin "1") (pinfunction "1_1") (pintype "passive"))
      (node (ref "R16") (pin "2") (pinfunction "2_2") (pintype "passive"))
      (node (ref "R17") (pin "2") (pinfunction "2_2") (pintype "passive"))
      (node (ref "R3") (pin "2") (pinfunction "2_2") (pintype "passive"))
      (node (ref "SW1") (pin "3") (pinfunction "3_3") (pintype "passive"))
      (node (ref "SW1") (pin "4") (pinfunction "4_4") (pintype "passive"))
      (node (ref "SW2") (pin "3") (pinfunction "3_3") (pintype "passive"))
      (node (ref "SW2") (pin "4") (pinfunction "4_4") (pintype "passive"))
      (node (ref "U1") (pin "1") (pinfunction "GND_1_1") (pintype "passive"))
      (node (ref "U1") (pin "2") (pinfunction "GND_2_2") (pintype "passive"))
      (node (ref "U1") (pin "42") (pinfunction "GND_42_42") (pintype "passive"))
      (node (ref "U1") (pin "43") (pinfunction "GND_43_43") (pintype "passive"))
      (node (ref "U1") (pin "46") (pinfunction "GND_46_46") (pintype "passive"))
      (node (ref "U1") (pin "47") (pinfunction "GND_47_47") (pintype "passive"))
      (node (ref "U1") (pin "48") (pinfunction "GND_48_48") (pintype "passive"))
      (node (ref "U1") (pin "49") (pinfunction "GND_49_49") (pintype "passive"))
      (node (ref "U1") (pin "50") (pinfunction "GND_50_50") (pintype "passive"))
      (node (ref "U1") (pin "51") (pinfunction "GND_51_51") (pintype "passive"))
      (node (ref "U1") (pin "52") (pinfunction "GND_52_52") (pintype "passive"))
      (node (ref "U1") (pin "53") (pinfunction "GND_53_53") (pintype "passive"))
      (node (ref "U1") (pin "54") (pinfunction "GND_54_54") (pintype "passive"))
      (node (ref "U1") (pin "55") (pinfunction "GND_55_55") (pintype "passive"))
      (node (ref "U1") (pin "56") (pinfunction "GND_56_56") (pintype "passive"))
      (node (ref "U1") (pin "57") (pinfunction "GND_57_57") (pintype "passive"))
      (node (ref "U1") (pin "58") (pinfunction "GND_58_58") (pintype "passive"))
      (node (ref "U1") (pin "59") (pinfunction "GND_59_59") (pintype "passive"))
      (node (ref "U1") (pin "60") (pinfunction "GND_60_60") (pintype "passive"))
      (node (ref "U1") (pin "61") (pinfunction "GND_61_61") (pintype "passive"))
      (node (ref "U1") (pin "62") (pinfunction "GND_62_62") (pintype "passive"))
      (node (ref "U1") (pin "63") (pinfunction "GND_63_63") (pintype "passive"))
      (node (ref "U1") (pin "64") (pinfunction "GND_64_64") (pintype "passive"))
      (node (ref "U1") (pin "65") (pinfunction "GND_65_65") (pintype "passive"))
      (node (ref "U1") (pin "66") (pinfunction "GND_66_66") (pintype "passive"))
      (node (ref "U1") (pin "67") (pinfunction "GND_67_67") (pintype "passive"))
      (node (ref "U1") (pin "68") (pinfunction "GND_68_68") (pintype "passive"))
      (node (ref "U1") (pin "69") (pinfunction "GND_69_69") (pintype "passive"))
      (node (ref "U1") (pin "70") (pinfunction "GND_70_70") (pintype "passive"))
      (node (ref "U1") (pin "71") (pinfunction "GND_71_71") (pintype "passive"))
      (node (ref "U1") (pin "72") (pinfunction "GND_72_72") (pintype "passive"))
      (node (ref "U1") (pin "73") (pinfunction "GND_73_73") (pintype "passive"))
      (node (ref "U2") (pin "13") (pinfunction "GND_13") (pintype "passive"))
      (node (ref "U2") (pin "21") (pinfunction "GND_21") (pintype "passive"))
      (node (ref "U2") (pin "3") (pinfunction "GND_3") (pintype "passive"))
      (node (ref "U3") (pin "2") (pinfunction "GND_2") (pintype "power_in"))
      (node (ref "U3") (pin "4") (pinfunction "GND_4") (pintype "power_in"))
    )
    (net (code "64") (name "Net-(D2-A)") (class "Default")
      (node (ref "D2") (pin "2") (pinfunction "A_2") (pintype "passive"))
      (node (ref "R5") (pin "1") (pinfunction "1_1") (pintype "passive"))
    )
    (net (code "65") (name "Net-(D3-A)") (class "Default")
      (node (ref "D3") (pin "2") (pinfunction "A_2") (pintype "passive"))
      (node (ref "R6") (pin "1") (pinfunction "1_1") (pintype "passive"))
    )
    (net (code "66") (name "Net-(J3-CC1)") (class "Default")
      (node (ref "J3") (pin "A5") (pinfunction "CC1_A5") (pintype "passive"))
      (node (ref "R3") (pin "1") (pinfunction "1_1") (pintype "passive"))
    )
    (net (code "67") (name "Net-(J3-CC2)") (class "Default")
      (node (ref "J3") (pin "B5") (pinfunction "CC2_B5") (pintype "passive"))
      (node (ref "R12") (pin "1") (pinfunction "1_1") (pintype "passive"))
    )
    (net (code "68") (name "Net-(J4-CC1)") (class "Default")
      (node (ref "J4") (pin "A5") (pinfunction "CC1_A5") (pintype "passive"))
      (node (ref "R16") (pin "1") (pinfunction "1_1") (pintype "passive"))
    )
    (net (code "69") (name "Net-(J4-CC2)") (class "Default")
      (node (ref "J4") (pin "B5") (pinfunction "CC2_B5") (pintype "passive"))
      (node (ref "R17") (pin "1") (pinfunction "1_1") (pintype "passive"))
    )
    (net (code "70") (name "Net-(Q1-B)") (class "Default")
      (node (ref "Q1") (pin "1") (pinfunction "B_1") (pintype "passive"))
      (node (ref "R4") (pin "1") (pinfunction "1_1") (pintype "passive"))
    )
    (net (code "71") (name "Net-(Q2-B)") (class "Default")
      (node (ref "Q2") (pin "1") (pinfunction "B_1") (pintype "passive"))
      (node (ref "R10") (pin "1") (pinfunction "1_1") (pintype "passive"))
    )
    (net (code "72") (name "Net-(U2-CBUS0)") (class "Default")
      (node (ref "R13") (pin "1") (pinfunction "1_1") (pintype "passive"))
      (node (ref "U2") (pin "15") (pinfunction "CBUS0_15") (pintype "passive"))
    )
    (net (code "73") (name "VCC_3V3") (class "Default")
      (node (ref "C11") (pin "1") (pinfunction "1_1") (pintype "passive"))
      (node (ref "C12") (pin "2") (pinfunction "2_2") (pintype "passive"))
      (node (ref "C13") (pin "1") (pinfunction "1_1") (pintype "passive"))
      (node (ref "C14") (pin "1") (pinfunction "1_1") (pintype "passive"))
      (node (ref "J1") (pin "2") (pinfunction "2_2") (pintype "passive"))
      (node (ref "J2") (pin "1") (pinfunction "1_1") (pintype "passive"))
      (node (ref "J6") (pin "2") (pinfunction "2_2") (pintype "passive"))
      (node (ref "R2") (pin "1") (pinfunction "1_1") (pintype "passive"))
      (node (ref "R20") (pin "2") (pinfunction "2_2") (pintype "passive"))
      (node (ref "R5") (pin "2") (pinfunction "2_2") (pintype "passive"))
      (node (ref "R6") (pin "2") (pinfunction "2_2") (pintype "passive"))
      (node (ref "R7") (pin "1") (pinfunction "1_1") (pintype "passive"))
      (node (ref "U1") (pin "3") (pinfunction "3V3_3") (pintype "passive"))
    )
    (net (code "74") (name "unconnected-(J1-Pad24)") (class "Default")
      (node (ref "J1") (pin "24") (pinfunction "24_24") (pintype "passive+no_connect"))
    )
    (net (code "75") (name "unconnected-(J3-SBU1-PadA8)") (class "Default")
      (node (ref "J3") (pin "A8") (pinfunction "SBU1_A8") (pintype "passive+no_connect"))
    )
    (net (code "76") (name "unconnected-(J3-SBU2-PadB8)") (class "Default")
      (node (ref "J3") (pin "B8") (pinfunction "SBU2_B8") (pintype "passive+no_connect"))
    )
    (net (code "77") (name "unconnected-(J4-SBU1-PadA8)") (class "Default")
      (node (ref "J4") (pin "A8") (pinfunction "SBU1_A8") (pintype "passive+no_connect"))
    )
    (net (code "78") (name "unconnected-(J4-SBU2-PadB8)") (class "Default")
      (node (ref "J4") (pin "B8") (pinfunction "SBU2_B8") (pintype "passive+no_connect"))
    )
    (net (code "79") (name "unconnected-(U2-CBUS1-Pad14)") (class "Default")
      (node (ref "U2") (pin "14") (pinfunction "CBUS1_14") (pintype "passive+no_connect"))
    )
    (net (code "80") (name "unconnected-(U2-CBUS2-Pad7)") (class "Default")
      (node (ref "U2") (pin "7") (pinfunction "CBUS2_7") (pintype "passive+no_connect"))
    )
    (net (code "81") (name "unconnected-(U2-~{CTS}-Pad6)") (class "Default")
      (node (ref "U2") (pin "6") (pinfunction "~{CTS}_6") (pintype "passive+no_connect"))
    )
    (net (code "82") (name "unconnected-(U2-~{DCD}-Pad5)") (class "Default")
      (node (ref "U2") (pin "5") (pinfunction "~{DCD}_5") (pintype "passive+no_connect"))
    )
    (net (code "83") (name "unconnected-(U2-~{DSR}-Pad4)") (class "Default")
      (node (ref "U2") (pin "4") (pinfunction "~{DSR}_4") (pintype "passive+no_connect"))
    )
    (net (code "84") (name "unconnected-(U2-~{RI}-Pad2)") (class "Default")
      (node (ref "U2") (pin "2") (pinfunction "~{RI}_2") (pintype "passive+no_connect"))
    )
  )
)
